# thermocoupleMv1.net
KiCad netlist of a schematic drawn in EAGLE
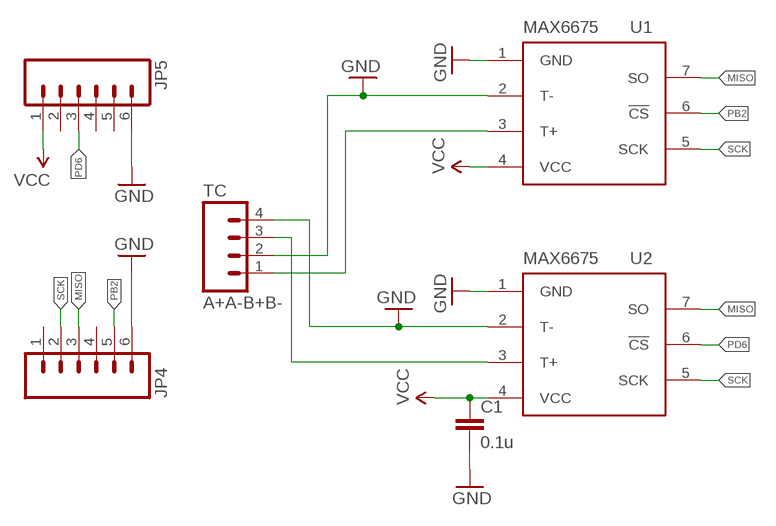
[diagram p0: schematic, sheet 1]

(export (version "E")
  (design (tool "Eeschema 10.0.6"))
  (components
    (comp (ref "C1")
      (value "0.1u")
      (footprint "eagle-import:0805")
      (libsource (lib "eagle-import") (part "CAP0805"))
    )
    (comp (ref "JP4")
      (value "M06LOCK_LONGPADS")
      (footprint "eagle-import:1X06_LOCK_LONGPADS")
      (libsource (lib "eagle-import") (part "M06LOCK_LONGPADS"))
    )
    (comp (ref "JP5")
      (value "M06LOCK_LONGPADS")
      (footprint "eagle-import:1X06_LOCK_LONGPADS")
      (libsource (lib "eagle-import") (part "M06LOCK_LONGPADS"))
    )
    (comp (ref "TC")
      (value "A+A-B+B-")
      (footprint "eagle-import:1X04_LOCK_LONGPADS")
      (libsource (lib "eagle-import") (part "M04LOCK_LONGPADS"))
    )
    (comp (ref "U1")
      (value "MAX6675")
      (footprint "eagle-import:SO08")
      (libsource (lib "eagle-import") (part "MAX6675"))
    )
    (comp (ref "U2")
      (value "MAX6675")
      (footprint "eagle-import:SO08")
      (libsource (lib "eagle-import") (part "MAX6675"))
    )
  )
  (nets
    (net (code "1") (name "GND") (class "Default")
      (node (ref "C1") (pin "2") (pinfunction "2_2") (pintype "passive"))
      (node (ref "JP4") (pin "6") (pinfunction "6_6") (pintype "passive"))
      (node (ref "JP5") (pin "6") (pinfunction "6_6") (pintype "passive"))
      (node (ref "TC") (pin "2") (pinfunction "2_2") (pintype "passive"))
      (node (ref "TC") (pin "4") (pinfunction "4_4") (pintype "passive"))
      (node (ref "U1") (pin "1") (pinfunction "GND_1") (pintype "bidirectional"))
      (node (ref "U1") (pin "2") (pinfunction "T-_2") (pintype "bidirectional"))
      (node (ref "U2") (pin "1") (pinfunction "GND_1") (pintype "bidirectional"))
      (node (ref "U2") (pin "2") (pinfunction "T-_2") (pintype "bidirectional"))
    )
    (net (code "2") (name "MISO") (class "Default")
      (node (ref "JP4") (pin "3") (pinfunction "3_3") (pintype "passive"))
      (node (ref "U1") (pin "7") (pinfunction "SO_7") (pintype "bidirectional"))
      (node (ref "U2") (pin "7") (pinfunction "SO_7") (pintype "bidirectional"))
    )
    (net (code "3") (name "Net-(U1-T+)") (class "Default")
      (node (ref "TC") (pin "1") (pinfunction "1_1") (pintype "passive"))
      (node (ref "U1") (pin "3") (pinfunction "T+_3") (pintype "bidirectional"))
    )
    (net (code "4") (name "Net-(U2-T+)") (class "Default")
      (node (ref "TC") (pin "3") (pinfunction "3_3") (pintype "passive"))
      (node (ref "U2") (pin "3") (pinfunction "T+_3") (pintype "bidirectional"))
    )
    (net (code "5") (name "PB2") (class "Default")
      (node (ref "JP4") (pin "5") (pinfunction "5_5") (pintype "passive"))
      (node (ref "U1") (pin "6") (pinfunction "~{CS}_6") (pintype "bidirectional"))
    )
    (net (code "6") (name "PD6") (class "Default")
      (node (ref "JP5") (pin "3") (pinfunction "3_3") (pintype "passive"))
      (node (ref "U2") (pin "6") (pinfunction "~{CS}_6") (pintype "bidirectional"))
    )
    (net (code "7") (name "SCK") (class "Default")
      (node (ref "JP4") (pin "2") (pinfunction "2_2") (pintype "passive"))
      (node (ref "U1") (pin "5") (pinfunction "SCK_5") (pintype "bidirectional"))
      (node (ref "U2") (pin "5") (pinfunction "SCK_5") (pintype "bidirectional"))
    )
    (net (code "8") (name "VCC") (class "Default")
      (node (ref "C1") (pin "1") (pinfunction "1_1") (pintype "passive"))
      (node (ref "JP5") (pin "1") (pinfunction "1_1") (pintype "passive"))
      (node (ref "U1") (pin "4") (pinfunction "VCC_4") (pintype "bidirectional"))
      (node (ref "U2") (pin "4") (pinfunction "VCC_4") (pintype "bidirectional"))
    )
    (net (code "9") (name "unconnected-(JP4-Pad1)") (class "Default")
      (node (ref "JP4") (pin "1") (pinfunction "1_1") (pintype "passive"))
    )
    (net (code "10") (name "unconnected-(JP4-Pad4)") (class "Default")
      (node (ref "JP4") (pin "4") (pinfunction "4_4") (pintype "passive"))
    )
    (net (code "11") (name "unconnected-(JP5-Pad2)") (class "Default")
      (node (ref "JP5") (pin "2") (pinfunction "2_2") (pintype "passive"))
    )
    (net (code "12") (name "unconnected-(JP5-Pad4)") (class "Default")
      (node (ref "JP5") (pin "4") (pinfunction "4_4") (pintype "passive"))
    )
    (net (code "13") (name "unconnected-(JP5-Pad5)") (class "Default")
      (node (ref "JP5") (pin "5") (pinfunction "5_5") (pintype "passive"))
    )
  )
)
